# lc2p.net
KiCad netlist of a schematic drawn in EAGLE
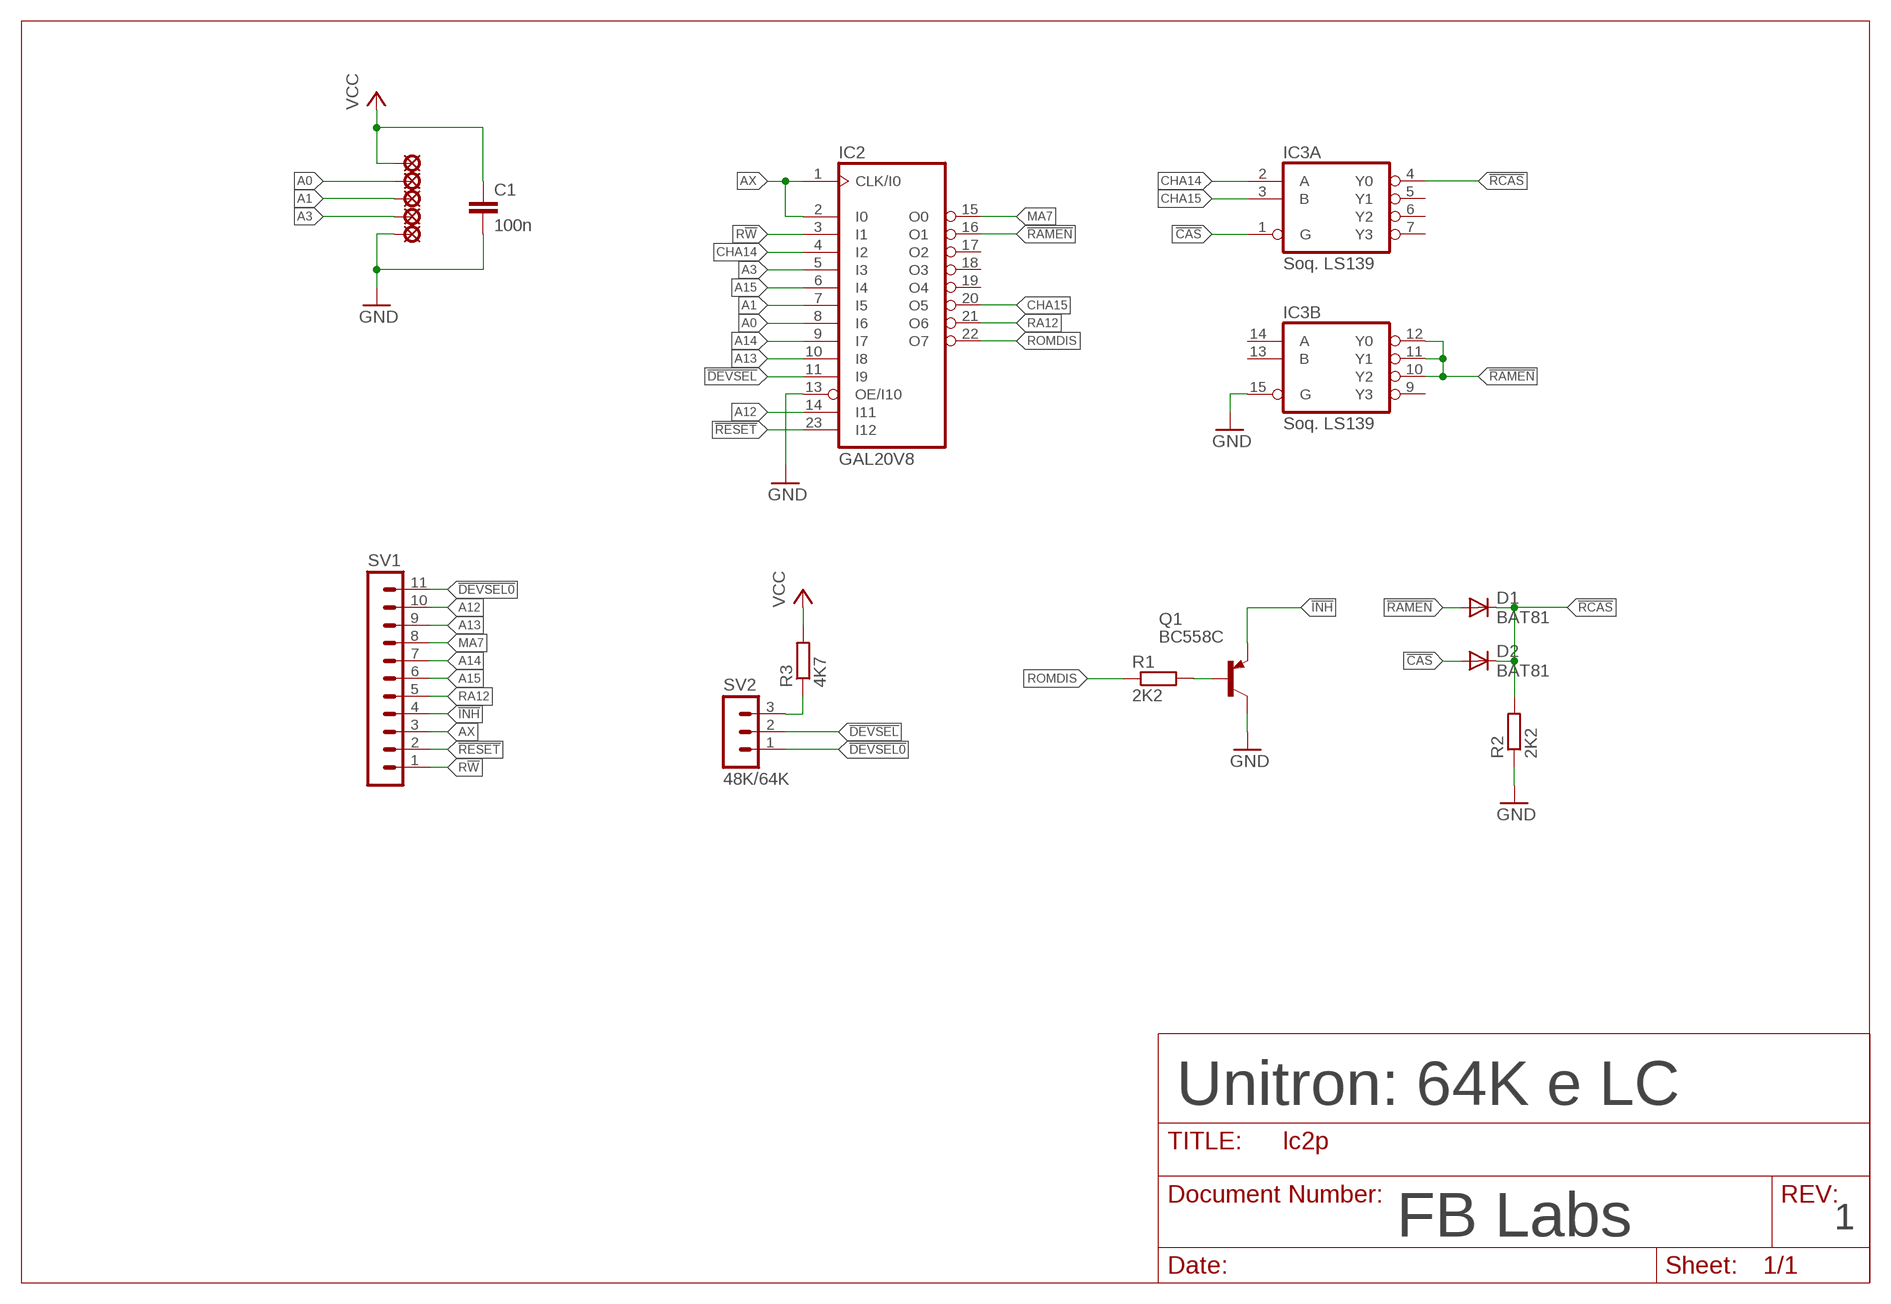
[diagram p0: schematic, sheet 1]

(export (version "E")
  (design (tool "Eeschema 10.0.6"))
  (components
    (comp (ref "C1")
      (value "100n")
      (footprint "eagle-import:C050-024X044")
      (libsource (lib "eagle-import") (part "C-EU050-024X044"))
    )
    (comp (ref "D1")
      (value "BAT81")
      (footprint "eagle-import:DO34-7")
      (libsource (lib "eagle-import") (part "BAT81"))
    )
    (comp (ref "D2")
      (value "BAT81")
      (footprint "eagle-import:DO34-7")
      (libsource (lib "eagle-import") (part "BAT81"))
    )
    (comp (ref "IC2")
      (value "GAL20V8")
      (footprint "eagle-import:DIL24-3")
      (fields (field (name "MF") "FARNELL") (field (name "MPN") "GAL20V8B-25QP"))
      (libsource (lib "eagle-import") (part "20V8"))
    )
    (comp (ref "IC3")
      (value "Soq. LS139")
      (footprint "eagle-import:DIL16")
      (libsource (lib "eagle-import") (part "74139NAC"))
    )
    (comp (ref "LSP1")
      (value "LSP10")
      (footprint "eagle-import:LSP10")
      (libsource (lib "eagle-import") (part "LSP10"))
    )
    (comp (ref "LSP2")
      (value "LSP10")
      (footprint "eagle-import:LSP10")
      (libsource (lib "eagle-import") (part "LSP10"))
    )
    (comp (ref "LSP3")
      (value "LSP10")
      (footprint "eagle-import:LSP10")
      (libsource (lib "eagle-import") (part "LSP10"))
    )
    (comp (ref "LSP4")
      (value "LSP10")
      (footprint "eagle-import:LSP10")
      (libsource (lib "eagle-import") (part "LSP10"))
    )
    (comp (ref "LSP5")
      (value "LSP10")
      (footprint "eagle-import:LSP10")
      (libsource (lib "eagle-import") (part "LSP10"))
    )
    (comp (ref "Q1")
      (value "BC558C")
      (footprint "eagle-import:TO92-EBC")
      (libsource (lib "eagle-import") (part "BC558C"))
    )
    (comp (ref "R1")
      (value "2K2")
      (footprint "eagle-import:0207_7")
      (libsource (lib "eagle-import") (part "R-EU_0207/7"))
    )
    (comp (ref "R2")
      (value "2K2")
      (footprint "eagle-import:0207_7")
      (libsource (lib "eagle-import") (part "R-EU_0207/7"))
    )
    (comp (ref "R3")
      (value "4K7")
      (footprint "eagle-import:0207_7")
      (libsource (lib "eagle-import") (part "R-EU_0207/7"))
    )
    (comp (ref "SV1")
      (value "MA11-1")
      (footprint "eagle-import:MA11-1")
      (libsource (lib "eagle-import") (part "MA11-1"))
    )
    (comp (ref "SV2")
      (value "48K/64K")
      (footprint "eagle-import:MA03-1-1")
      (libsource (lib "eagle-import") (part "MA03-1MA03-1-1"))
    )
  )
  (nets
    (net (code "1") (name "/R~{W}") (class "Default")
      (node (ref "IC2") (pin "3") (pinfunction "I1_3") (pintype "input"))
      (node (ref "SV1") (pin "1") (pinfunction "1_1") (pintype "passive"))
    )
    (net (code "2") (name "/~{CAS}") (class "Default")
      (node (ref "D2") (pin "A") (pinfunction "A_A") (pintype "passive"))
      (node (ref "IC3") (pin "1") (pinfunction "G_1") (pintype "input"))
    )
    (net (code "3") (name "/~{DEVSEL0}") (class "Default")
      (node (ref "SV1") (pin "11") (pinfunction "11_11") (pintype "passive"))
      (node (ref "SV2") (pin "1") (pinfunction "1_1") (pintype "passive"))
    )
    (net (code "4") (name "/~{DEVSEL}") (class "Default")
      (node (ref "IC2") (pin "11") (pinfunction "I9_11") (pintype "input"))
      (node (ref "SV2") (pin "2") (pinfunction "2_2") (pintype "passive"))
    )
    (net (code "5") (name "/~{INH}") (class "Default")
      (node (ref "Q1") (pin "E") (pinfunction "E_E") (pintype "passive"))
      (node (ref "SV1") (pin "4") (pinfunction "4_4") (pintype "passive"))
    )
    (net (code "6") (name "/~{RAMEN}") (class "Default")
      (node (ref "D1") (pin "A") (pinfunction "A_A") (pintype "passive"))
      (node (ref "IC2") (pin "16") (pinfunction "O1_16") (pintype "bidirectional"))
      (node (ref "IC3") (pin "10") (pinfunction "Y2_10") (pintype "output"))
      (node (ref "IC3") (pin "11") (pinfunction "Y1_11") (pintype "output"))
      (node (ref "IC3") (pin "12") (pinfunction "Y0_12") (pintype "output"))
    )
    (net (code "7") (name "/~{RCAS}") (class "Default")
      (node (ref "D1") (pin "C") (pinfunction "C_C") (pintype "passive"))
      (node (ref "D2") (pin "C") (pinfunction "C_C") (pintype "passive"))
      (node (ref "IC3") (pin "4") (pinfunction "Y0_4") (pintype "output"))
      (node (ref "R2") (pin "2") (pinfunction "2_2") (pintype "passive"))
    )
    (net (code "8") (name "/~{RESET}") (class "Default")
      (node (ref "IC2") (pin "23") (pinfunction "I12_23") (pintype "input"))
      (node (ref "SV1") (pin "2") (pinfunction "2_2") (pintype "passive"))
    )
    (net (code "9") (name "A0") (class "Default")
      (node (ref "IC2") (pin "8") (pinfunction "I6_8") (pintype "input"))
      (node (ref "LSP1") (pin "MP") (pinfunction "MP_MP") (pintype "passive"))
    )
    (net (code "10") (name "A1") (class "Default")
      (node (ref "IC2") (pin "7") (pinfunction "I5_7") (pintype "input"))
      (node (ref "LSP2") (pin "MP") (pinfunction "MP_MP") (pintype "passive"))
    )
    (net (code "11") (name "A3") (class "Default")
      (node (ref "IC2") (pin "5") (pinfunction "I3_5") (pintype "input"))
      (node (ref "LSP3") (pin "MP") (pinfunction "MP_MP") (pintype "passive"))
    )
    (net (code "12") (name "A12") (class "Default")
      (node (ref "IC2") (pin "14") (pinfunction "I11_14") (pintype "input"))
      (node (ref "SV1") (pin "10") (pinfunction "10_10") (pintype "passive"))
    )
    (net (code "13") (name "A13") (class "Default")
      (node (ref "IC2") (pin "10") (pinfunction "I8_10") (pintype "input"))
      (node (ref "SV1") (pin "9") (pinfunction "9_9") (pintype "passive"))
    )
    (net (code "14") (name "A14") (class "Default")
      (node (ref "IC2") (pin "9") (pinfunction "I7_9") (pintype "input"))
      (node (ref "SV1") (pin "7") (pinfunction "7_7") (pintype "passive"))
    )
    (net (code "15") (name "A15") (class "Default")
      (node (ref "IC2") (pin "6") (pinfunction "I4_6") (pintype "input"))
      (node (ref "SV1") (pin "6") (pinfunction "6_6") (pintype "passive"))
    )
    (net (code "16") (name "AX") (class "Default")
      (node (ref "IC2") (pin "1") (pinfunction "CLK/I0_1") (pintype "input"))
      (node (ref "IC2") (pin "2") (pinfunction "I0_2") (pintype "input"))
      (node (ref "SV1") (pin "3") (pinfunction "3_3") (pintype "passive"))
    )
    (net (code "17") (name "CHA14") (class "Default")
      (node (ref "IC2") (pin "4") (pinfunction "I2_4") (pintype "input"))
      (node (ref "IC3") (pin "2") (pinfunction "A_2") (pintype "input"))
    )
    (net (code "18") (name "CHA15") (class "Default")
      (node (ref "IC2") (pin "20") (pinfunction "O5_20") (pintype "bidirectional"))
      (node (ref "IC3") (pin "3") (pinfunction "B_3") (pintype "input"))
    )
    (net (code "19") (name "GND") (class "Default")
      (node (ref "C1") (pin "2") (pinfunction "2_2") (pintype "passive"))
      (node (ref "IC2") (pin "13") (pinfunction "OE/I10_13") (pintype "input"))
      (node (ref "IC3") (pin "15") (pinfunction "G_15") (pintype "input"))
      (node (ref "LSP4") (pin "MP") (pinfunction "MP_MP") (pintype "passive"))
      (node (ref "Q1") (pin "C") (pinfunction "C_C") (pintype "passive"))
      (node (ref "R2") (pin "1") (pinfunction "1_1") (pintype "passive"))
    )
    (net (code "20") (name "MA7") (class "Default")
      (node (ref "IC2") (pin "15") (pinfunction "O0_15") (pintype "bidirectional"))
      (node (ref "SV1") (pin "8") (pinfunction "8_8") (pintype "passive"))
    )
    (net (code "21") (name "Net-(Q1-PadB)") (class "Default")
      (node (ref "Q1") (pin "B") (pinfunction "B_B") (pintype "passive"))
      (node (ref "R1") (pin "2") (pinfunction "2_2") (pintype "passive"))
    )
    (net (code "22") (name "Net-(R3-Pad1)") (class "Default")
      (node (ref "R3") (pin "1") (pinfunction "1_1") (pintype "passive"))
      (node (ref "SV2") (pin "3") (pinfunction "3_3") (pintype "passive"))
    )
    (net (code "23") (name "RA12") (class "Default")
      (node (ref "IC2") (pin "21") (pinfunction "O6_21") (pintype "bidirectional"))
      (node (ref "SV1") (pin "5") (pinfunction "5_5") (pintype "passive"))
    )
    (net (code "24") (name "ROMDIS") (class "Default")
      (node (ref "IC2") (pin "22") (pinfunction "O7_22") (pintype "bidirectional"))
      (node (ref "R1") (pin "1") (pinfunction "1_1") (pintype "passive"))
    )
    (net (code "25") (name "VCC") (class "Default")
      (node (ref "C1") (pin "1") (pinfunction "1_1") (pintype "passive"))
      (node (ref "LSP5") (pin "MP") (pinfunction "MP_MP") (pintype "passive"))
      (node (ref "R3") (pin "2") (pinfunction "2_2") (pintype "passive"))
    )
    (net (code "26") (name "unconnected-(IC2A-O2-Pad17)") (class "Default")
      (node (ref "IC2") (pin "17") (pinfunction "O2_17") (pintype "bidirectional"))
    )
    (net (code "27") (name "unconnected-(IC2A-O3-Pad18)") (class "Default")
      (node (ref "IC2") (pin "18") (pinfunction "O3_18") (pintype "bidirectional"))
    )
    (net (code "28") (name "unconnected-(IC2A-O4-Pad19)") (class "Default")
      (node (ref "IC2") (pin "19") (pinfunction "O4_19") (pintype "bidirectional"))
    )
    (net (code "29") (name "unconnected-(IC3A-Y1-Pad5)") (class "Default")
      (node (ref "IC3") (pin "5") (pinfunction "Y1_5") (pintype "output"))
    )
    (net (code "30") (name "unconnected-(IC3A-Y2-Pad6)") (class "Default")
      (node (ref "IC3") (pin "6") (pinfunction "Y2_6") (pintype "output"))
    )
    (net (code "31") (name "unconnected-(IC3A-Y3-Pad7)") (class "Default")
      (node (ref "IC3") (pin "7") (pinfunction "Y3_7") (pintype "output"))
    )
    (net (code "32") (name "unconnected-(IC3B-A-Pad14)") (class "Default")
      (node (ref "IC3") (pin "14") (pinfunction "A_14") (pintype "input"))
    )
    (net (code "33") (name "unconnected-(IC3B-B-Pad13)") (class "Default")
      (node (ref "IC3") (pin "13") (pinfunction "B_13") (pintype "input"))
    )
    (net (code "34") (name "unconnected-(IC3B-Y3-Pad9)") (class "Default")
      (node (ref "IC3") (pin "9") (pinfunction "Y3_9") (pintype "output"))
    )
  )
)
